# Analog_Electronics_Fundamentals_103_-_La.net
KiCad netlist of a schematic drawn in EAGLE
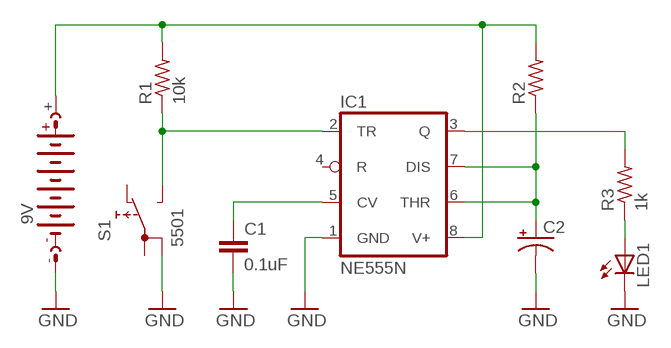
[diagram p0: schematic, sheet 1]

(export (version "E")
  (design (tool "Eeschema 10.0.6"))
  (components
    (comp (ref "9V")
      (value "AB9V")
      (footprint "eagle-import:AB9V")
      (libsource (lib "eagle-import") (part "AB9V"))
    )
    (comp (ref "C1")
      (value "0.1uF")
      (footprint "eagle-import:C025-024X044")
      (libsource (lib "eagle-import") (part "C-EU025-024X044"))
    )
    (comp (ref "C2")
      (value "CPOL-USTT5D11")
      (footprint "eagle-import:TT5D11")
      (libsource (lib "eagle-import") (part "CPOL-USTT5D11"))
    )
    (comp (ref "IC1")
      (value "NE555N")
      (footprint "eagle-import:DIL08")
      (libsource (lib "eagle-import") (part "555NNE"))
    )
    (comp (ref "LED1")
      (value "LED5MM")
      (footprint "eagle-import:LED5MM")
      (libsource (lib "eagle-import") (part "LED5MM"))
    )
    (comp (ref "R1")
      (value "10k")
      (footprint "eagle-import:0204_7")
      (libsource (lib "eagle-import") (part "R-US_0204/7"))
    )
    (comp (ref "R2")
      (value "R-US_0204/7")
      (footprint "eagle-import:0204_7")
      (libsource (lib "eagle-import") (part "R-US_0204/7"))
    )
    (comp (ref "R3")
      (value "1k")
      (footprint "eagle-import:0204_7")
      (libsource (lib "eagle-import") (part "R-US_0204/7"))
    )
    (comp (ref "S1")
      (value "5501")
      (footprint "eagle-import:5501")
      (libsource (lib "eagle-import") (part "55?01"))
    )
  )
  (nets
    (net (code "1") (name "GND") (class "Default")
      (node (ref "9V") (pin "-") (pinfunction "-_-") (pintype "passive"))
      (node (ref "C1") (pin "2") (pinfunction "2_2") (pintype "passive"))
      (node (ref "C2") (pin "-") (pinfunction "-_-") (pintype "passive"))
      (node (ref "IC1") (pin "1") (pinfunction "GND_1") (pintype "power_in"))
      (node (ref "LED1") (pin "K") (pinfunction "C_K") (pintype "passive"))
      (node (ref "S1") (pin "1B") (pinfunction "1B_1B") (pintype "passive"))
    )
    (net (code "2") (name "Net-(IC1-CV)") (class "Default")
      (node (ref "C1") (pin "1") (pinfunction "1_1") (pintype "passive"))
      (node (ref "IC1") (pin "5") (pinfunction "CV_5") (pintype "input"))
    )
    (net (code "3") (name "Net-(IC1-DIS)") (class "Default")
      (node (ref "C2") (pin "+") (pinfunction "+_+") (pintype "passive"))
      (node (ref "IC1") (pin "6") (pinfunction "THR_6") (pintype "input"))
      (node (ref "IC1") (pin "7") (pinfunction "DIS_7") (pintype "input"))
      (node (ref "R2") (pin "1") (pinfunction "1_1") (pintype "passive"))
    )
    (net (code "4") (name "Net-(IC1-Q)") (class "Default")
      (node (ref "IC1") (pin "3") (pinfunction "Q_3") (pintype "output"))
      (node (ref "R3") (pin "2") (pinfunction "2_2") (pintype "passive"))
    )
    (net (code "5") (name "Net-(IC1-TR)") (class "Default")
      (node (ref "IC1") (pin "2") (pinfunction "TR_2") (pintype "input"))
      (node (ref "R1") (pin "1") (pinfunction "1_1") (pintype "passive"))
      (node (ref "S1") (pin "NO") (pinfunction "NO_NO") (pintype "passive"))
    )
    (net (code "6") (name "Net-(IC1-V+)") (class "Default")
      (node (ref "9V") (pin "+") (pinfunction "+_+") (pintype "passive"))
      (node (ref "IC1") (pin "8") (pinfunction "V+_8") (pintype "power_in"))
      (node (ref "R1") (pin "2") (pinfunction "2_2") (pintype "passive"))
      (node (ref "R2") (pin "2") (pinfunction "2_2") (pintype "passive"))
    )
    (net (code "7") (name "Net-(LED1-PadA)") (class "Default")
      (node (ref "LED1") (pin "A") (pinfunction "A_A") (pintype "passive"))
      (node (ref "R3") (pin "1") (pinfunction "1_1") (pintype "passive"))
    )
    (net (code "8") (name "unconnected-(IC1-R-Pad4)") (class "Default")
      (node (ref "IC1") (pin "4") (pinfunction "R_4") (pintype "input"))
    )
    (net (code "9") (name "unconnected-(S1-Pad1A)") (class "Default")
      (node (ref "S1") (pin "1A") (pinfunction "1A_1A") (pintype "passive"))
    )
    (net (code "10") (name "unconnected-(S1-PadNC)") (class "Default")
      (node (ref "S1") (pin "NC") (pinfunction "NC_NC") (pintype "passive"))
    )
  )
)
